# Version3.net
KiCad netlist of a schematic drawn in EAGLE
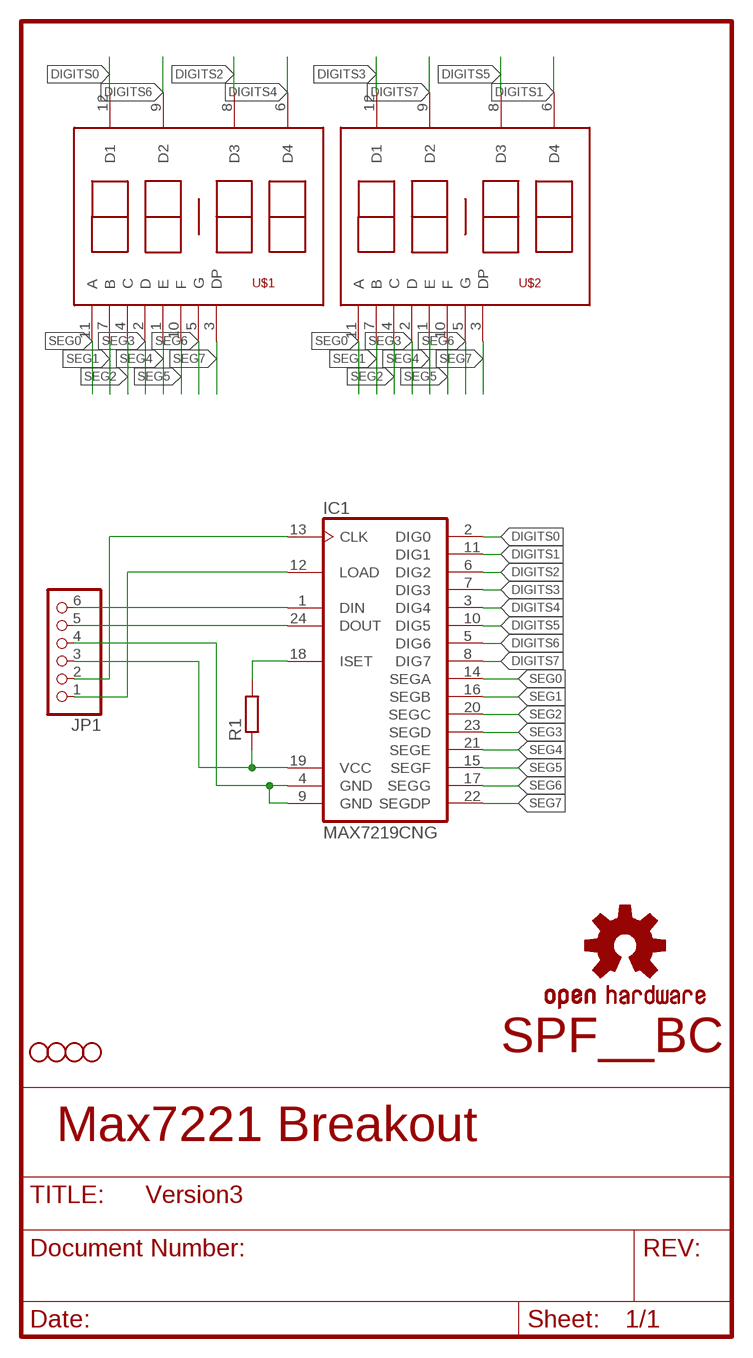
[diagram p0: schematic, sheet 1]

(export (version "E")
  (design (tool "Eeschema 10.0.6"))
  (components
    (comp (ref "H1")
      (value "STAND-OFF")
      (footprint "eagle-import:STAND-OFF")
      (libsource (lib "eagle-import") (part "STAND-OFF"))
    )
    (comp (ref "H2")
      (value "STAND-OFF")
      (footprint "eagle-import:STAND-OFF")
      (libsource (lib "eagle-import") (part "STAND-OFF"))
    )
    (comp (ref "H3")
      (value "STAND-OFF")
      (footprint "eagle-import:STAND-OFF")
      (libsource (lib "eagle-import") (part "STAND-OFF"))
    )
    (comp (ref "H4")
      (value "STAND-OFF")
      (footprint "eagle-import:STAND-OFF")
      (libsource (lib "eagle-import") (part "STAND-OFF"))
    )
    (comp (ref "IC1")
      (value "MAX7219CNG")
      (footprint "eagle-import:DIL24-3")
      (fields (field (name "MF") "MAXIM"))
      (libsource (lib "eagle-import") (part "MAX7219CNG"))
    )
    (comp (ref "JP1")
      (value "PINHD-1X6CLEAN")
      (footprint "eagle-import:1X06-CLEAN")
      (libsource (lib "eagle-import") (part "PINHD-1X6CLEAN"))
    )
    (comp (ref "LOGO1")
      (value "OSHW-LOGOL")
      (footprint "eagle-import:OSHW-LOGO-L")
      (libsource (lib "eagle-import") (part "OSHW-LOGOL"))
    )
    (comp (ref "R1")
      (value "R-EU_0207/10")
      (footprint "eagle-import:0207_10")
      (libsource (lib "eagle-import") (part "R-EU_0207/10"))
    )
    (comp (ref "U$1")
      (value "4DIG_7SEG_CATHODE")
      (footprint "eagle-import:4DIG_7SEG_CLOCK")
      (libsource (lib "eagle-import") (part "4DIG_7SEG_CATHODE"))
    )
    (comp (ref "U$2")
      (value "4DIG_7SEG_CATHODE")
      (footprint "eagle-import:4DIG_7SEG_CLOCK")
      (libsource (lib "eagle-import") (part "4DIG_7SEG_CATHODE"))
    )
  )
  (nets
    (net (code "1") (name "DIGITS0") (class "Default")
      (node (ref "IC1") (pin "2") (pinfunction "DIG0_2") (pintype "output"))
      (node (ref "U$1") (pin "12") (pinfunction "D1_12") (pintype "bidirectional"))
    )
    (net (code "2") (name "DIGITS1") (class "Default")
      (node (ref "IC1") (pin "11") (pinfunction "DIG1_11") (pintype "output"))
      (node (ref "U$2") (pin "6") (pinfunction "D4_6") (pintype "bidirectional"))
    )
    (net (code "3") (name "DIGITS2") (class "Default")
      (node (ref "IC1") (pin "6") (pinfunction "DIG2_6") (pintype "output"))
      (node (ref "U$1") (pin "8") (pinfunction "D3_8") (pintype "bidirectional"))
    )
    (net (code "4") (name "DIGITS3") (class "Default")
      (node (ref "IC1") (pin "7") (pinfunction "DIG3_7") (pintype "output"))
      (node (ref "U$2") (pin "12") (pinfunction "D1_12") (pintype "bidirectional"))
    )
    (net (code "5") (name "DIGITS4") (class "Default")
      (node (ref "IC1") (pin "3") (pinfunction "DIG4_3") (pintype "output"))
      (node (ref "U$1") (pin "6") (pinfunction "D4_6") (pintype "bidirectional"))
    )
    (net (code "6") (name "DIGITS5") (class "Default")
      (node (ref "IC1") (pin "10") (pinfunction "DIG5_10") (pintype "output"))
      (node (ref "U$2") (pin "8") (pinfunction "D3_8") (pintype "bidirectional"))
    )
    (net (code "7") (name "DIGITS6") (class "Default")
      (node (ref "IC1") (pin "5") (pinfunction "DIG6_5") (pintype "output"))
      (node (ref "U$1") (pin "9") (pinfunction "D2_9") (pintype "bidirectional"))
    )
    (net (code "8") (name "DIGITS7") (class "Default")
      (node (ref "IC1") (pin "8") (pinfunction "DIG7_8") (pintype "output"))
      (node (ref "U$2") (pin "9") (pinfunction "D2_9") (pintype "bidirectional"))
    )
    (net (code "9") (name "Net-(IC1-CLK)") (class "Default")
      (node (ref "IC1") (pin "13") (pinfunction "CLK_13") (pintype "input"))
      (node (ref "JP1") (pin "2") (pinfunction "2_2") (pintype "passive"))
    )
    (net (code "10") (name "Net-(IC1-DIN)") (class "Default")
      (node (ref "IC1") (pin "1") (pinfunction "DIN_1") (pintype "input"))
      (node (ref "JP1") (pin "6") (pinfunction "6_6") (pintype "passive"))
    )
    (net (code "11") (name "Net-(IC1-DOUT)") (class "Default")
      (node (ref "IC1") (pin "24") (pinfunction "DOUT_24") (pintype "output"))
      (node (ref "JP1") (pin "5") (pinfunction "5_5") (pintype "passive"))
    )
    (net (code "12") (name "Net-(IC1-GND-Pad4)") (class "Default")
      (node (ref "IC1") (pin "4") (pinfunction "GND_4") (pintype "power_in"))
      (node (ref "IC1") (pin "9") (pinfunction "GND_9") (pintype "power_in"))
      (node (ref "JP1") (pin "4") (pinfunction "4_4") (pintype "passive"))
    )
    (net (code "13") (name "Net-(IC1-ISET)") (class "Default")
      (node (ref "IC1") (pin "18") (pinfunction "ISET_18") (pintype "input"))
      (node (ref "R1") (pin "2") (pinfunction "2_2") (pintype "passive"))
    )
    (net (code "14") (name "Net-(IC1-LOAD)") (class "Default")
      (node (ref "IC1") (pin "12") (pinfunction "LOAD_12") (pintype "input"))
      (node (ref "JP1") (pin "1") (pinfunction "1_1") (pintype "passive"))
    )
    (net (code "15") (name "Net-(IC1-VCC)") (class "Default")
      (node (ref "IC1") (pin "19") (pinfunction "VCC_19") (pintype "power_in"))
      (node (ref "JP1") (pin "3") (pinfunction "3_3") (pintype "passive"))
      (node (ref "R1") (pin "1") (pinfunction "1_1") (pintype "passive"))
    )
    (net (code "16") (name "SEG0") (class "Default")
      (node (ref "IC1") (pin "14") (pinfunction "SEGA_14") (pintype "output"))
      (node (ref "U$1") (pin "11") (pinfunction "A_11") (pintype "bidirectional"))
      (node (ref "U$2") (pin "11") (pinfunction "A_11") (pintype "bidirectional"))
    )
    (net (code "17") (name "SEG1") (class "Default")
      (node (ref "IC1") (pin "16") (pinfunction "SEGB_16") (pintype "output"))
      (node (ref "U$1") (pin "7") (pinfunction "B_7") (pintype "bidirectional"))
      (node (ref "U$2") (pin "7") (pinfunction "B_7") (pintype "bidirectional"))
    )
    (net (code "18") (name "SEG2") (class "Default")
      (node (ref "IC1") (pin "20") (pinfunction "SEGC_20") (pintype "output"))
      (node (ref "U$1") (pin "4") (pinfunction "C_4") (pintype "bidirectional"))
      (node (ref "U$2") (pin "4") (pinfunction "C_4") (pintype "bidirectional"))
    )
    (net (code "19") (name "SEG3") (class "Default")
      (node (ref "IC1") (pin "23") (pinfunction "SEGD_23") (pintype "output"))
      (node (ref "U$1") (pin "2") (pinfunction "D_2") (pintype "bidirectional"))
      (node (ref "U$2") (pin "2") (pinfunction "D_2") (pintype "bidirectional"))
    )
    (net (code "20") (name "SEG4") (class "Default")
      (node (ref "IC1") (pin "21") (pinfunction "SEGE_21") (pintype "output"))
      (node (ref "U$1") (pin "1") (pinfunction "E_1") (pintype "bidirectional"))
      (node (ref "U$2") (pin "1") (pinfunction "E_1") (pintype "bidirectional"))
    )
    (net (code "21") (name "SEG5") (class "Default")
      (node (ref "IC1") (pin "15") (pinfunction "SEGF_15") (pintype "output"))
      (node (ref "U$1") (pin "10") (pinfunction "F_10") (pintype "bidirectional"))
      (node (ref "U$2") (pin "10") (pinfunction "F_10") (pintype "bidirectional"))
    )
    (net (code "22") (name "SEG6") (class "Default")
      (node (ref "IC1") (pin "17") (pinfunction "SEGG_17") (pintype "output"))
      (node (ref "U$1") (pin "5") (pinfunction "G_5") (pintype "bidirectional"))
      (node (ref "U$2") (pin "5") (pinfunction "G_5") (pintype "bidirectional"))
    )
    (net (code "23") (name "SEG7") (class "Default")
      (node (ref "IC1") (pin "22") (pinfunction "SEGDP_22") (pintype "output"))
      (node (ref "U$1") (pin "3") (pinfunction "DP_3") (pintype "bidirectional"))
      (node (ref "U$2") (pin "3") (pinfunction "DP_3") (pintype "bidirectional"))
    )
  )
)
